# PCB_Motor_Robot.net
KiCad netlist of a schematic drawn in EAGLE
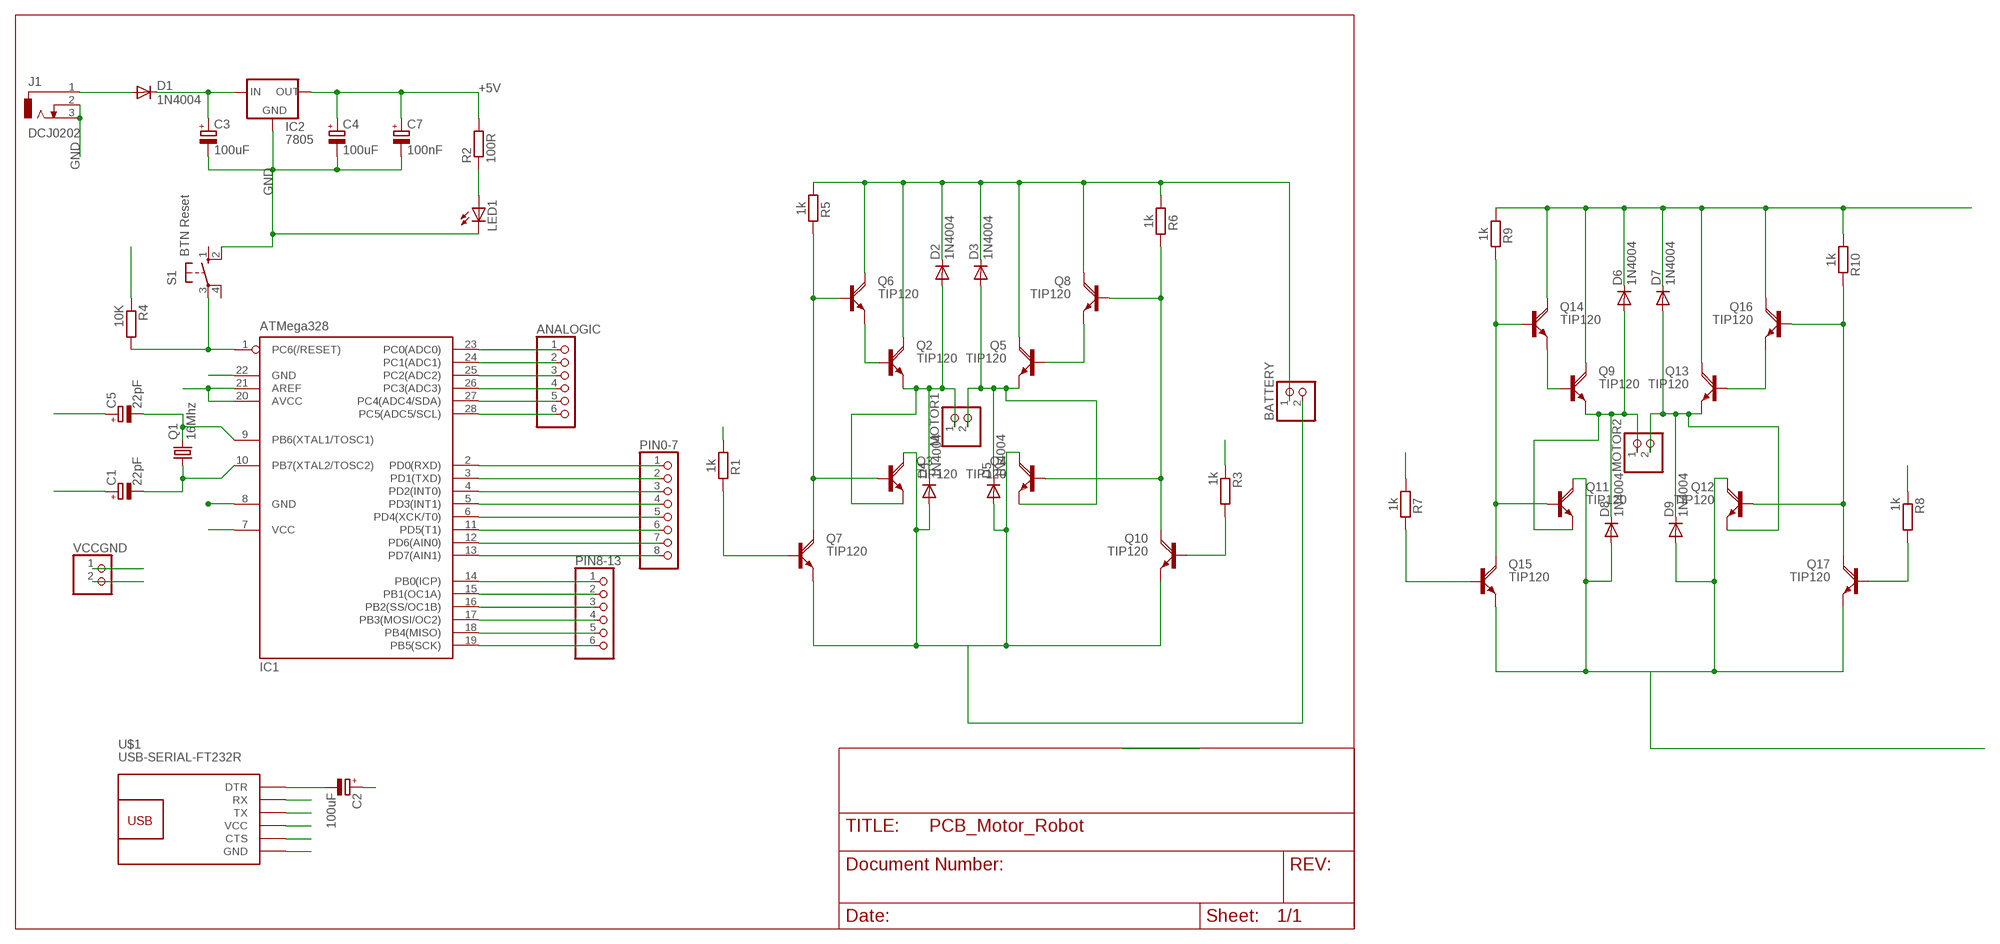
[diagram p0: schematic, sheet 1]

(export (version "E")
  (design (tool "Eeschema 10.0.6"))
  (components
    (comp (ref "ANALOGIC")
      (value "PINHD-1X6")
      (footprint "eagle-import:1X06")
      (libsource (lib "eagle-import") (part "PINHD-1X6"))
    )
    (comp (ref "BATTERY")
      (value "PINHD-1X2")
      (footprint "eagle-import:1X02")
      (libsource (lib "eagle-import") (part "PINHD-1X2"))
    )
    (comp (ref "C1")
      (value "22pF")
      (footprint "eagle-import:E2,5-5")
      (libsource (lib "eagle-import") (part "CPOL-EUE2.5-5"))
    )
    (comp (ref "C2")
      (value "100uF")
      (footprint "eagle-import:TAP5-50")
      (libsource (lib "eagle-import") (part "CPOL-EUTAP5-50"))
    )
    (comp (ref "C3")
      (value "100uF")
      (footprint "eagle-import:TAP5-50")
      (libsource (lib "eagle-import") (part "CPOL-EUTAP5-50"))
    )
    (comp (ref "C4")
      (value "100uF")
      (footprint "eagle-import:TAP5-50")
      (libsource (lib "eagle-import") (part "CPOL-EUTAP5-50"))
    )
    (comp (ref "C5")
      (value "22pF")
      (footprint "eagle-import:E2,5-5")
      (libsource (lib "eagle-import") (part "CPOL-EUE2.5-5"))
    )
    (comp (ref "C7")
      (value "100nF")
      (footprint "eagle-import:E2,5-5")
      (libsource (lib "eagle-import") (part "CPOL-EUE2.5-5"))
    )
    (comp (ref "D1")
      (value "1N4004")
      (footprint "eagle-import:DO41-10")
      (libsource (lib "eagle-import") (part "1N4004"))
    )
    (comp (ref "D2")
      (value "1N4004")
      (footprint "eagle-import:DO41-10")
      (libsource (lib "eagle-import") (part "1N4004"))
    )
    (comp (ref "D3")
      (value "1N4004")
      (footprint "eagle-import:DO41-10")
      (libsource (lib "eagle-import") (part "1N4004"))
    )
    (comp (ref "D4")
      (value "1N4004")
      (footprint "eagle-import:DO41-10")
      (libsource (lib "eagle-import") (part "1N4004"))
    )
    (comp (ref "D5")
      (value "1N4004")
      (footprint "eagle-import:DO41-10")
      (libsource (lib "eagle-import") (part "1N4004"))
    )
    (comp (ref "D6")
      (value "1N4004")
      (footprint "eagle-import:DO41-10")
      (libsource (lib "eagle-import") (part "1N4004"))
    )
    (comp (ref "D7")
      (value "1N4004")
      (footprint "eagle-import:DO41-10")
      (libsource (lib "eagle-import") (part "1N4004"))
    )
    (comp (ref "D8")
      (value "1N4004")
      (footprint "eagle-import:DO41-10")
      (libsource (lib "eagle-import") (part "1N4004"))
    )
    (comp (ref "D9")
      (value "1N4004")
      (footprint "eagle-import:DO41-10")
      (libsource (lib "eagle-import") (part "1N4004"))
    )
    (comp (ref "IC1")
      (value "ATMega328")
      (footprint "eagle-import:DIL28-3")
      (libsource (lib "eagle-import") (part "MEGA8-P"))
    )
    (comp (ref "IC2")
      (value "7805")
      (footprint "eagle-import:78XXL")
      (libsource (lib "eagle-import") (part "78XXL"))
    )
    (comp (ref "J1")
      (value "DCJ0202")
      (footprint "eagle-import:DCJ0202")
      (libsource (lib "eagle-import") (part "DCJ0202"))
    )
    (comp (ref "LED1")
      (value "LED5MM")
      (footprint "eagle-import:LED5MM")
      (libsource (lib "eagle-import") (part "LED5MM"))
    )
    (comp (ref "MOTOR1")
      (value "PINHD-1X2")
      (footprint "eagle-import:1X02")
      (libsource (lib "eagle-import") (part "PINHD-1X2"))
    )
    (comp (ref "MOTOR2")
      (value "PINHD-1X2")
      (footprint "eagle-import:1X02")
      (libsource (lib "eagle-import") (part "PINHD-1X2"))
    )
    (comp (ref "PIN0-7")
      (value "PINHD-1X8")
      (footprint "eagle-import:1X08")
      (libsource (lib "eagle-import") (part "PINHD-1X8"))
    )
    (comp (ref "PIN8-13")
      (value "PINHD-1X6")
      (footprint "eagle-import:1X06")
      (libsource (lib "eagle-import") (part "PINHD-1X6"))
    )
    (comp (ref "Q1")
      (value "16Mhz")
      (footprint "eagle-import:HC49_S")
      (libsource (lib "eagle-import") (part "CRYSTALHC49S"))
    )
    (comp (ref "Q2")
      (value "TIP120")
      (footprint "eagle-import:TO220AH")
      (libsource (lib "eagle-import") (part "TIP120"))
    )
    (comp (ref "Q3")
      (value "TIP120")
      (footprint "eagle-import:TO220AH")
      (libsource (lib "eagle-import") (part "TIP120"))
    )
    (comp (ref "Q4")
      (value "TIP120")
      (footprint "eagle-import:TO220AH")
      (libsource (lib "eagle-import") (part "TIP120"))
    )
    (comp (ref "Q5")
      (value "TIP120")
      (footprint "eagle-import:TO220AH")
      (libsource (lib "eagle-import") (part "TIP120"))
    )
    (comp (ref "Q6")
      (value "TIP120")
      (footprint "eagle-import:TO220AH")
      (libsource (lib "eagle-import") (part "TIP120"))
    )
    (comp (ref "Q7")
      (value "TIP120")
      (footprint "eagle-import:TO220AH")
      (libsource (lib "eagle-import") (part "TIP120"))
    )
    (comp (ref "Q8")
      (value "TIP120")
      (footprint "eagle-import:TO220AH")
      (libsource (lib "eagle-import") (part "TIP120"))
    )
    (comp (ref "Q9")
      (value "TIP120")
      (footprint "eagle-import:TO220AH")
      (libsource (lib "eagle-import") (part "TIP120"))
    )
    (comp (ref "Q10")
      (value "TIP120")
      (footprint "eagle-import:TO220AH")
      (libsource (lib "eagle-import") (part "TIP120"))
    )
    (comp (ref "Q11")
      (value "TIP120")
      (footprint "eagle-import:TO220AH")
      (libsource (lib "eagle-import") (part "TIP120"))
    )
    (comp (ref "Q12")
      (value "TIP120")
      (footprint "eagle-import:TO220AH")
      (libsource (lib "eagle-import") (part "TIP120"))
    )
    (comp (ref "Q13")
      (value "TIP120")
      (footprint "eagle-import:TO220AH")
      (libsource (lib "eagle-import") (part "TIP120"))
    )
    (comp (ref "Q14")
      (value "TIP120")
      (footprint "eagle-import:TO220AH")
      (libsource (lib "eagle-import") (part "TIP120"))
    )
    (comp (ref "Q15")
      (value "TIP120")
      (footprint "eagle-import:TO220AH")
      (libsource (lib "eagle-import") (part "TIP120"))
    )
    (comp (ref "Q16")
      (value "TIP120")
      (footprint "eagle-import:TO220AH")
      (libsource (lib "eagle-import") (part "TIP120"))
    )
    (comp (ref "Q17")
      (value "TIP120")
      (footprint "eagle-import:TO220AH")
      (libsource (lib "eagle-import") (part "TIP120"))
    )
    (comp (ref "R1")
      (value "1k")
      (footprint "eagle-import:0204_7")
      (libsource (lib "eagle-import") (part "R-EU_0204/7"))
    )
    (comp (ref "R2")
      (value "100R")
      (footprint "eagle-import:0204_7")
      (libsource (lib "eagle-import") (part "R-EU_0204/7"))
    )
    (comp (ref "R3")
      (value "1k")
      (footprint "eagle-import:0204_7")
      (libsource (lib "eagle-import") (part "R-EU_0204/7"))
    )
    (comp (ref "R4")
      (value "10K")
      (footprint "eagle-import:0204_7")
      (libsource (lib "eagle-import") (part "R-EU_0204/7"))
    )
    (comp (ref "R5")
      (value "1k")
      (footprint "eagle-import:0204_7")
      (libsource (lib "eagle-import") (part "R-EU_0204/7"))
    )
    (comp (ref "R6")
      (value "1k")
      (footprint "eagle-import:0204_7")
      (libsource (lib "eagle-import") (part "R-EU_0204/7"))
    )
    (comp (ref "R7")
      (value "1k")
      (footprint "eagle-import:0204_7")
      (libsource (lib "eagle-import") (part "R-EU_0204/7"))
    )
    (comp (ref "R8")
      (value "1k")
      (footprint "eagle-import:0204_7")
      (libsource (lib "eagle-import") (part "R-EU_0204/7"))
    )
    (comp (ref "R9")
      (value "1k")
      (footprint "eagle-import:0204_7")
      (libsource (lib "eagle-import") (part "R-EU_0204/7"))
    )
    (comp (ref "R10")
      (value "1k")
      (footprint "eagle-import:0204_7")
      (libsource (lib "eagle-import") (part "R-EU_0204/7"))
    )
    (comp (ref "S1")
      (value "BTN Reset")
      (footprint "eagle-import:B3F-10XX")
      (fields (field (name "MPN") "B3F-1000"))
      (libsource (lib "eagle-import") (part "10-XX"))
    )
    (comp (ref "U$1")
      (value "USB-SERIAL-FT232R")
      (footprint "eagle-import:USB-SERIAL-FT232R")
      (libsource (lib "eagle-import") (part "USB-SERIAL-FT232R"))
    )
    (comp (ref "VCCGND")
      (value "PINHD-1X2")
      (footprint "eagle-import:1X02")
      (libsource (lib "eagle-import") (part "PINHD-1X2"))
    )
  )
  (nets
    (net (code "1") (name "/+5V") (class "Default")
      (node (ref "C4") (pin "+") (pinfunction "+_+") (pintype "passive"))
      (node (ref "C7") (pin "+") (pinfunction "+_+") (pintype "passive"))
      (node (ref "IC1") (pin "20") (pinfunction "AVCC_20") (pintype "power_in"))
      (node (ref "IC1") (pin "21") (pinfunction "AREF_21") (pintype "passive"))
      (node (ref "IC1") (pin "7") (pinfunction "VCC_7") (pintype "power_in"))
      (node (ref "IC2") (pin "OUT") (pinfunction "OUT_OUT") (pintype "passive"))
      (node (ref "R2") (pin "2") (pinfunction "2_2") (pintype "passive"))
      (node (ref "R4") (pin "1") (pinfunction "1_1") (pintype "passive"))
      (node (ref "U$1") (pin "4") (pinfunction "VCC_4") (pintype "power_in"))
      (node (ref "VCCGND") (pin "1") (pinfunction "1_1") (pintype "passive"))
    )
    (net (code "2") (name "/GND") (class "Default")
      (node (ref "BATTERY") (pin "2") (pinfunction "2_2") (pintype "passive"))
      (node (ref "C1") (pin "+") (pinfunction "+_+") (pintype "passive"))
      (node (ref "C3") (pin "-") (pinfunction "-_-") (pintype "passive"))
      (node (ref "C4") (pin "-") (pinfunction "-_-") (pintype "passive"))
      (node (ref "C5") (pin "+") (pinfunction "+_+") (pintype "passive"))
      (node (ref "C7") (pin "-") (pinfunction "-_-") (pintype "passive"))
      (node (ref "D4") (pin "A") (pinfunction "A_A") (pintype "passive"))
      (node (ref "D5") (pin "A") (pinfunction "A_A") (pintype "passive"))
      (node (ref "D8") (pin "A") (pinfunction "A_A") (pintype "passive"))
      (node (ref "D9") (pin "A") (pinfunction "A_A") (pintype "passive"))
      (node (ref "IC1") (pin "22") (pinfunction "GND_22") (pintype "power_in"))
      (node (ref "IC1") (pin "8") (pinfunction "GND_8") (pintype "power_in"))
      (node (ref "IC2") (pin "GND") (pinfunction "GND_GND") (pintype "input"))
      (node (ref "J1") (pin "2") (pinfunction "2_2") (pintype "passive"))
      (node (ref "J1") (pin "3") (pinfunction "3_3") (pintype "passive"))
      (node (ref "LED1") (pin "K") (pinfunction "C_K") (pintype "passive"))
      (node (ref "Q10") (pin "E") (pinfunction "E_E") (pintype "passive"))
      (node (ref "Q11") (pin "C") (pinfunction "C_C") (pintype "passive"))
      (node (ref "Q12") (pin "C") (pinfunction "C_C") (pintype "passive"))
      (node (ref "Q15") (pin "E") (pinfunction "E_E") (pintype "passive"))
      (node (ref "Q17") (pin "E") (pinfunction "E_E") (pintype "passive"))
      (node (ref "Q3") (pin "C") (pinfunction "C_C") (pintype "passive"))
      (node (ref "Q4") (pin "C") (pinfunction "C_C") (pintype "passive"))
      (node (ref "Q7") (pin "E") (pinfunction "E_E") (pintype "passive"))
      (node (ref "S1") (pin "2") (pinfunction "S1_2") (pintype "passive"))
      (node (ref "U$1") (pin "6") (pinfunction "GND_6") (pintype "bidirectional"))
      (node (ref "VCCGND") (pin "2") (pinfunction "2_2") (pintype "passive"))
    )
    (net (code "3") (name "/M1-A1") (class "Default")
      (node (ref "IC1") (pin "17") (pinfunction "PB3(MOSI/OC2)_17") (pintype "bidirectional"))
      (node (ref "PIN8-13") (pin "4") (pinfunction "4_4") (pintype "passive"))
      (node (ref "R3") (pin "1") (pinfunction "1_1") (pintype "passive"))
    )
    (net (code "4") (name "/M1-B1") (class "Default")
      (node (ref "IC1") (pin "16") (pinfunction "PB2(SS/OC1B)_16") (pintype "bidirectional"))
      (node (ref "PIN8-13") (pin "3") (pinfunction "3_3") (pintype "passive"))
      (node (ref "R1") (pin "1") (pinfunction "1_1") (pintype "passive"))
    )
    (net (code "5") (name "/M2-A1") (class "Default")
      (node (ref "IC1") (pin "12") (pinfunction "PD6(AIN0)_12") (pintype "bidirectional"))
      (node (ref "PIN0-7") (pin "7") (pinfunction "7_7") (pintype "passive"))
      (node (ref "R8") (pin "1") (pinfunction "1_1") (pintype "passive"))
    )
    (net (code "6") (name "/M2-B1") (class "Default")
      (node (ref "IC1") (pin "11") (pinfunction "PD5(T1)_11") (pintype "bidirectional"))
      (node (ref "PIN0-7") (pin "6") (pinfunction "6_6") (pintype "passive"))
      (node (ref "R7") (pin "1") (pinfunction "1_1") (pintype "passive"))
    )
    (net (code "7") (name "/RESET") (class "Default")
      (node (ref "C2") (pin "+") (pinfunction "+_+") (pintype "passive"))
      (node (ref "IC1") (pin "1") (pinfunction "PC6(/RESET)_1") (pintype "bidirectional"))
      (node (ref "R4") (pin "2") (pinfunction "2_2") (pintype "passive"))
      (node (ref "S1") (pin "3") (pinfunction "P_3") (pintype "passive"))
    )
    (net (code "8") (name "/RX") (class "Default")
      (node (ref "IC1") (pin "2") (pinfunction "PD0(RXD)_2") (pintype "bidirectional"))
      (node (ref "PIN0-7") (pin "1") (pinfunction "1_1") (pintype "passive"))
      (node (ref "U$1") (pin "3") (pinfunction "TX_3") (pintype "bidirectional"))
    )
    (net (code "9") (name "/TX") (class "Default")
      (node (ref "IC1") (pin "3") (pinfunction "PD1(TXD)_3") (pintype "bidirectional"))
      (node (ref "PIN0-7") (pin "2") (pinfunction "2_2") (pintype "passive"))
      (node (ref "U$1") (pin "2") (pinfunction "RX_2") (pintype "bidirectional"))
    )
    (net (code "10") (name "/VCC-BAT") (class "Default")
      (node (ref "BATTERY") (pin "1") (pinfunction "1_1") (pintype "passive"))
      (node (ref "D2") (pin "C") (pinfunction "C_C") (pintype "passive"))
      (node (ref "D3") (pin "C") (pinfunction "C_C") (pintype "passive"))
      (node (ref "D6") (pin "C") (pinfunction "C_C") (pintype "passive"))
      (node (ref "D7") (pin "C") (pinfunction "C_C") (pintype "passive"))
      (node (ref "Q13") (pin "C") (pinfunction "C_C") (pintype "passive"))
      (node (ref "Q14") (pin "C") (pinfunction "C_C") (pintype "passive"))
      (node (ref "Q16") (pin "C") (pinfunction "C_C") (pintype "passive"))
      (node (ref "Q2") (pin "C") (pinfunction "C_C") (pintype "passive"))
      (node (ref "Q5") (pin "C") (pinfunction "C_C") (pintype "passive"))
      (node (ref "Q6") (pin "C") (pinfunction "C_C") (pintype "passive"))
      (node (ref "Q8") (pin "C") (pinfunction "C_C") (pintype "passive"))
      (node (ref "Q9") (pin "C") (pinfunction "C_C") (pintype "passive"))
      (node (ref "R10") (pin "1") (pinfunction "1_1") (pintype "passive"))
      (node (ref "R5") (pin "1") (pinfunction "1_1") (pintype "passive"))
      (node (ref "R6") (pin "1") (pinfunction "1_1") (pintype "passive"))
      (node (ref "R9") (pin "1") (pinfunction "1_1") (pintype "passive"))
    )
    (net (code "11") (name "Net-(C3-Pad+)") (class "Default")
      (node (ref "C3") (pin "+") (pinfunction "+_+") (pintype "passive"))
      (node (ref "D1") (pin "C") (pinfunction "C_C") (pintype "passive"))
      (node (ref "IC2") (pin "IN") (pinfunction "IN_IN") (pintype "input"))
    )
    (net (code "12") (name "Net-(D1-PadA)") (class "Default")
      (node (ref "D1") (pin "A") (pinfunction "A_A") (pintype "passive"))
      (node (ref "J1") (pin "1") (pinfunction "1_1") (pintype "passive"))
    )
    (net (code "13") (name "Net-(D2-PadA)") (class "Default")
      (node (ref "D2") (pin "A") (pinfunction "A_A") (pintype "passive"))
      (node (ref "D4") (pin "C") (pinfunction "C_C") (pintype "passive"))
      (node (ref "MOTOR1") (pin "1") (pinfunction "1_1") (pintype "passive"))
      (node (ref "Q2") (pin "E") (pinfunction "E_E") (pintype "passive"))
      (node (ref "Q3") (pin "E") (pinfunction "E_E") (pintype "passive"))
    )
    (net (code "14") (name "Net-(D3-PadA)") (class "Default")
      (node (ref "D3") (pin "A") (pinfunction "A_A") (pintype "passive"))
      (node (ref "D5") (pin "C") (pinfunction "C_C") (pintype "passive"))
      (node (ref "MOTOR1") (pin "2") (pinfunction "2_2") (pintype "passive"))
      (node (ref "Q4") (pin "E") (pinfunction "E_E") (pintype "passive"))
      (node (ref "Q5") (pin "E") (pinfunction "E_E") (pintype "passive"))
    )
    (net (code "15") (name "Net-(D6-PadA)") (class "Default")
      (node (ref "D6") (pin "A") (pinfunction "A_A") (pintype "passive"))
      (node (ref "D8") (pin "C") (pinfunction "C_C") (pintype "passive"))
      (node (ref "MOTOR2") (pin "1") (pinfunction "1_1") (pintype "passive"))
      (node (ref "Q11") (pin "E") (pinfunction "E_E") (pintype "passive"))
      (node (ref "Q9") (pin "E") (pinfunction "E_E") (pintype "passive"))
    )
    (net (code "16") (name "Net-(D7-PadA)") (class "Default")
      (node (ref "D7") (pin "A") (pinfunction "A_A") (pintype "passive"))
      (node (ref "D9") (pin "C") (pinfunction "C_C") (pintype "passive"))
      (node (ref "MOTOR2") (pin "2") (pinfunction "2_2") (pintype "passive"))
      (node (ref "Q12") (pin "E") (pinfunction "E_E") (pintype "passive"))
      (node (ref "Q13") (pin "E") (pinfunction "E_E") (pintype "passive"))
    )
    (net (code "17") (name "Net-(IC1-PB0(ICP))") (class "Default")
      (node (ref "IC1") (pin "14") (pinfunction "PB0(ICP)_14") (pintype "bidirectional"))
      (node (ref "PIN8-13") (pin "1") (pinfunction "1_1") (pintype "passive"))
    )
    (net (code "18") (name "Net-(IC1-PB1(OC1A))") (class "Default")
      (node (ref "IC1") (pin "15") (pinfunction "PB1(OC1A)_15") (pintype "bidirectional"))
      (node (ref "PIN8-13") (pin "2") (pinfunction "2_2") (pintype "passive"))
    )
    (net (code "19") (name "Net-(IC1-PB4(MISO))") (class "Default")
      (node (ref "IC1") (pin "18") (pinfunction "PB4(MISO)_18") (pintype "bidirectional"))
      (node (ref "PIN8-13") (pin "5") (pinfunction "5_5") (pintype "passive"))
    )
    (net (code "20") (name "Net-(IC1-PB5(SCK))") (class "Default")
      (node (ref "IC1") (pin "19") (pinfunction "PB5(SCK)_19") (pintype "bidirectional"))
      (node (ref "PIN8-13") (pin "6") (pinfunction "6_6") (pintype "passive"))
    )
    (net (code "21") (name "Net-(IC1-PB6(XTAL1{slash}TOSC1))") (class "Default")
      (node (ref "C5") (pin "-") (pinfunction "-_-") (pintype "passive"))
      (node (ref "IC1") (pin "9") (pinfunction "PB6(XTAL1/TOSC1)_9") (pintype "bidirectional"))
      (node (ref "Q1") (pin "2") (pinfunction "2_2") (pintype "passive"))
    )
    (net (code "22") (name "Net-(IC1-PB7(XTAL2{slash}TOSC2))") (class "Default")
      (node (ref "C1") (pin "-") (pinfunction "-_-") (pintype "passive"))
      (node (ref "IC1") (pin "10") (pinfunction "PB7(XTAL2/TOSC2)_10") (pintype "bidirectional"))
      (node (ref "Q1") (pin "1") (pinfunction "1_1") (pintype "passive"))
    )
    (net (code "23") (name "Net-(IC1-PC0(ADC0))") (class "Default")
      (node (ref "ANALOGIC") (pin "1") (pinfunction "1_1") (pintype "passive"))
      (node (ref "IC1") (pin "23") (pinfunction "PC0(ADC0)_23") (pintype "bidirectional"))
    )
    (net (code "24") (name "Net-(IC1-PC1(ADC1))") (class "Default")
      (node (ref "ANALOGIC") (pin "2") (pinfunction "2_2") (pintype "passive"))
      (node (ref "IC1") (pin "24") (pinfunction "PC1(ADC1)_24") (pintype "bidirectional"))
    )
    (net (code "25") (name "Net-(IC1-PC2(ADC2))") (class "Default")
      (node (ref "ANALOGIC") (pin "3") (pinfunction "3_3") (pintype "passive"))
      (node (ref "IC1") (pin "25") (pinfunction "PC2(ADC2)_25") (pintype "bidirectional"))
    )
    (net (code "26") (name "Net-(IC1-PC3(ADC3))") (class "Default")
      (node (ref "ANALOGIC") (pin "4") (pinfunction "4_4") (pintype "passive"))
      (node (ref "IC1") (pin "26") (pinfunction "PC3(ADC3)_26") (pintype "bidirectional"))
    )
    (net (code "27") (name "Net-(IC1-PC4(ADC4{slash}SDA))") (class "Default")
      (node (ref "ANALOGIC") (pin "5") (pinfunction "5_5") (pintype "passive"))
      (node (ref "IC1") (pin "27") (pinfunction "PC4(ADC4/SDA)_27") (pintype "bidirectional"))
    )
    (net (code "28") (name "Net-(IC1-PC5(ADC5{slash}SCL))") (class "Default")
      (node (ref "ANALOGIC") (pin "6") (pinfunction "6_6") (pintype "passive"))
      (node (ref "IC1") (pin "28") (pinfunction "PC5(ADC5/SCL)_28") (pintype "bidirectional"))
    )
    (net (code "29") (name "Net-(IC1-PD2(INT0))") (class "Default")
      (node (ref "IC1") (pin "4") (pinfunction "PD2(INT0)_4") (pintype "bidirectional"))
      (node (ref "PIN0-7") (pin "3") (pinfunction "3_3") (pintype "passive"))
    )
    (net (code "30") (name "Net-(IC1-PD3(INT1))") (class "Default")
      (node (ref "IC1") (pin "5") (pinfunction "PD3(INT1)_5") (pintype "bidirectional"))
      (node (ref "PIN0-7") (pin "4") (pinfunction "4_4") (pintype "passive"))
    )
    (net (code "31") (name "Net-(IC1-PD4(XCK{slash}T0))") (class "Default")
      (node (ref "IC1") (pin "6") (pinfunction "PD4(XCK/T0)_6") (pintype "bidirectional"))
      (node (ref "PIN0-7") (pin "5") (pinfunction "5_5") (pintype "passive"))
    )
    (net (code "32") (name "Net-(IC1-PD7(AIN1))") (class "Default")
      (node (ref "IC1") (pin "13") (pinfunction "PD7(AIN1)_13") (pintype "bidirectional"))
      (node (ref "PIN0-7") (pin "8") (pinfunction "8_8") (pintype "passive"))
    )
    (net (code "33") (name "Net-(LED1-PadA)") (class "Default")
      (node (ref "LED1") (pin "A") (pinfunction "A_A") (pintype "passive"))
      (node (ref "R2") (pin "1") (pinfunction "1_1") (pintype "passive"))
    )
    (net (code "34") (name "Net-(Q2-PadB)") (class "Default")
      (node (ref "Q2") (pin "B") (pinfunction "B_B") (pintype "passive"))
      (node (ref "Q6") (pin "E") (pinfunction "E_E") (pintype "passive"))
    )
    (net (code "35") (name "Net-(Q3-PadB)") (class "Default")
      (node (ref "Q3") (pin "B") (pinfunction "B_B") (pintype "passive"))
      (node (ref "Q6") (pin "B") (pinfunction "B_B") (pintype "passive"))
      (node (ref "Q7") (pin "C") (pinfunction "C_C") (pintype "passive"))
      (node (ref "R5") (pin "2") (pinfunction "2_2") (pintype "passive"))
    )
    (net (code "36") (name "Net-(Q5-PadB)") (class "Default")
      (node (ref "Q5") (pin "B") (pinfunction "B_B") (pintype "passive"))
      (node (ref "Q8") (pin "E") (pinfunction "E_E") (pintype "passive"))
    )
    (net (code "37") (name "Net-(Q7-PadB)") (class "Default")
      (node (ref "Q7") (pin "B") (pinfunction "B_B") (pintype "passive"))
      (node (ref "R1") (pin "2") (pinfunction "2_2") (pintype "passive"))
    )
    (net (code "38") (name "Net-(Q10-PadB)") (class "Default")
      (node (ref "Q10") (pin "B") (pinfunction "B_B") (pintype "passive"))
      (node (ref "R3") (pin "2") (pinfunction "2_2") (pintype "passive"))
    )
    (net (code "39") (name "Net-(Q10-PadC)") (class "Default")
      (node (ref "Q10") (pin "C") (pinfunction "C_C") (pintype "passive"))
      (node (ref "Q4") (pin "B") (pinfunction "B_B") (pintype "passive"))
      (node (ref "Q8") (pin "B") (pinfunction "B_B") (pintype "passive"))
      (node (ref "R6") (pin "2") (pinfunction "2_2") (pintype "passive"))
    )
    (net (code "40") (name "Net-(Q11-PadB)") (class "Default")
      (node (ref "Q11") (pin "B") (pinfunction "B_B") (pintype "passive"))
      (node (ref "Q14") (pin "B") (pinfunction "B_B") (pintype "passive"))
      (node (ref "Q15") (pin "C") (pinfunction "C_C") (pintype "passive"))
      (node (ref "R9") (pin "2") (pinfunction "2_2") (pintype "passive"))
    )
    (net (code "41") (name "Net-(Q12-PadB)") (class "Default")
      (node (ref "Q12") (pin "B") (pinfunction "B_B") (pintype "passive"))
      (node (ref "Q16") (pin "B") (pinfunction "B_B") (pintype "passive"))
      (node (ref "Q17") (pin "C") (pinfunction "C_C") (pintype "passive"))
      (node (ref "R10") (pin "2") (pinfunction "2_2") (pintype "passive"))
    )
    (net (code "42") (name "Net-(Q13-PadB)") (class "Default")
      (node (ref "Q13") (pin "B") (pinfunction "B_B") (pintype "passive"))
      (node (ref "Q16") (pin "E") (pinfunction "E_E") (pintype "passive"))
    )
    (net (code "43") (name "Net-(Q14-PadE)") (class "Default")
      (node (ref "Q14") (pin "E") (pinfunction "E_E") (pintype "passive"))
      (node (ref "Q9") (pin "B") (pinfunction "B_B") (pintype "passive"))
    )
    (net (code "44") (name "Net-(Q15-PadB)") (class "Default")
      (node (ref "Q15") (pin "B") (pinfunction "B_B") (pintype "passive"))
      (node (ref "R7") (pin "2") (pinfunction "2_2") (pintype "passive"))
    )
    (net (code "45") (name "Net-(Q17-PadB)") (class "Default")
      (node (ref "Q17") (pin "B") (pinfunction "B_B") (pintype "passive"))
      (node (ref "R8") (pin "2") (pinfunction "2_2") (pintype "passive"))
    )
    (net (code "46") (name "Net-(U$1-DTR)") (class "Default")
      (node (ref "C2") (pin "-") (pinfunction "-_-") (pintype "passive"))
      (node (ref "U$1") (pin "1") (pinfunction "DTR_1") (pintype "bidirectional"))
    )
    (net (code "47") (name "unconnected-(S1-P1-Pad4)") (class "Default")
      (node (ref "S1") (pin "4") (pinfunction "P1_4") (pintype "passive"))
    )
    (net (code "48") (name "unconnected-(S1-S-Pad1)") (class "Default")
      (node (ref "S1") (pin "1") (pinfunction "S_1") (pintype "passive"))
    )
    (net (code "49") (name "unconnected-(U$1-CTS-Pad5)") (class "Default")
      (node (ref "U$1") (pin "5") (pinfunction "CTS_5") (pintype "bidirectional"))
    )
  )
)
